# Ad_Hoc_Radio_Node_2005.net
KiCad netlist of a schematic drawn in Altium Designer
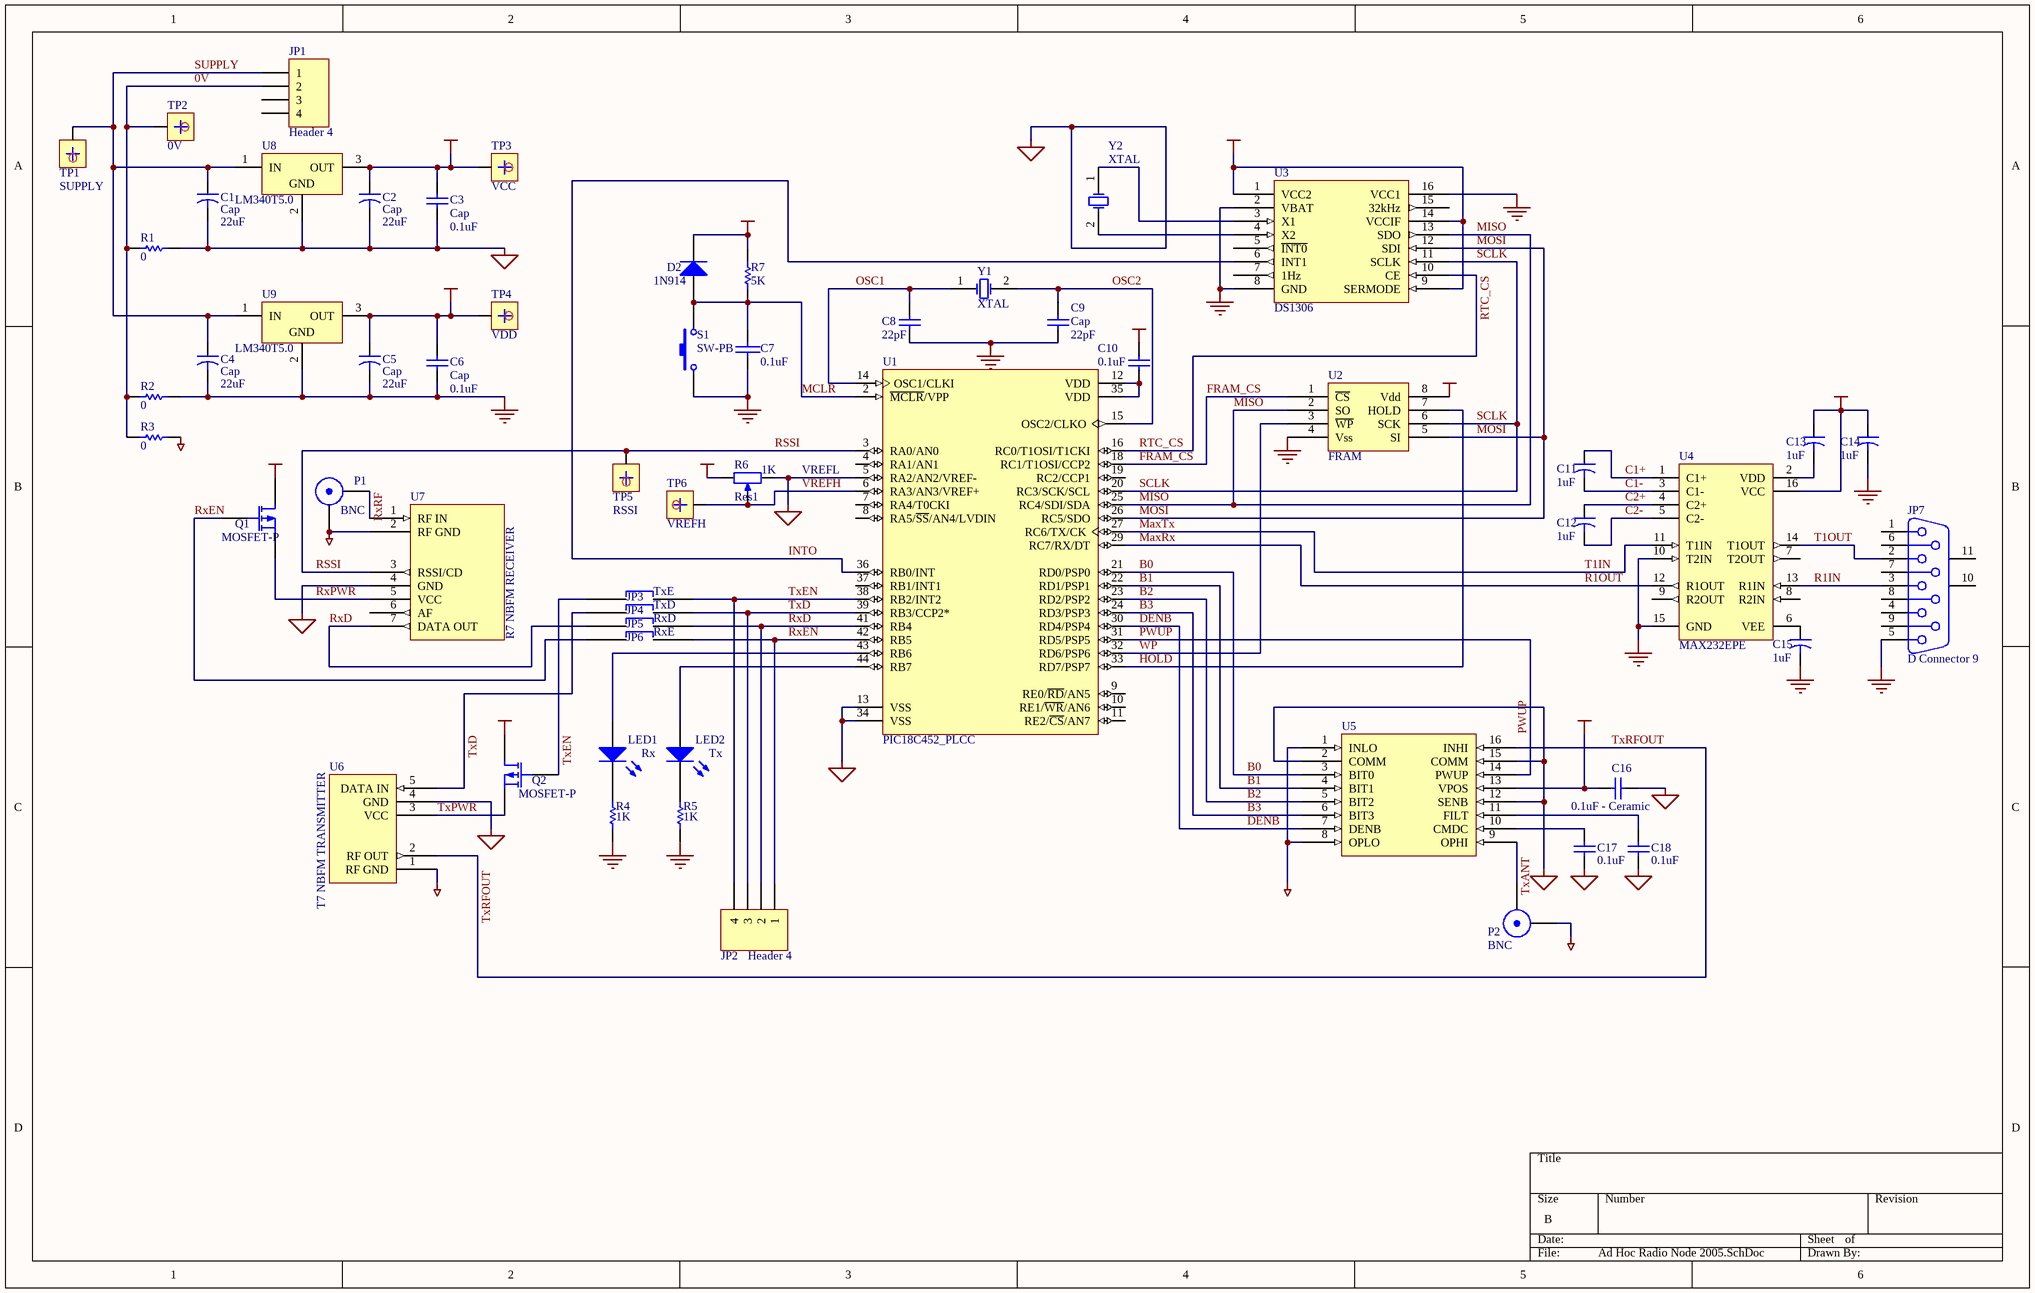
[diagram p0: Ad Hoc Radio Node 2005.SchDoc]

(export (version "E")
  (design (tool "Eeschema 10.0.6"))
  (components
    (comp (ref "C1")
      (value "Cap")
      (footprint "0.1 ELECTRO CAP")
      (description "Capacitor")
      (fields
        (field (name "MANUFACTURER") "Generic Components")
        (field (name "ALTIUM_VALUE") "22uF")
        (field (name "PUBLISHER") "Altium Limited")
      )
      (libsource (lib "Miscellaneous Devices") (part "Cap2"))
    )
    (comp (ref "C2")
      (value "Cap")
      (footprint "0.1 ELECTRO CAP")
      (description "Capacitor")
      (fields
        (field (name "MANUFACTURER") "Generic Components")
        (field (name "ALTIUM_VALUE") "22uF")
        (field (name "PUBLISHER") "Altium Limited")
      )
      (libsource (lib "Miscellaneous Devices") (part "Cap2"))
    )
    (comp (ref "C3")
      (value "Cap")
      (footprint "0.2 box cap")
      (description "Capacitor")
      (fields
        (field (name "MANUFACTURER") "Generic Components")
        (field (name "ALTIUM_VALUE") "0.1uF")
        (field (name "PUBLISHER") "Altium Limited")
      )
      (libsource (lib "Miscellaneous Devices") (part "Cap"))
    )
    (comp (ref "C4")
      (value "Cap")
      (footprint "0.1 RAD CAP")
      (description "Capacitor")
      (fields
        (field (name "MANUFACTURER") "Generic Components")
        (field (name "ALTIUM_VALUE") "22uF")
        (field (name "PUBLISHER") "Altium Limited")
      )
      (libsource (lib "Miscellaneous Devices") (part "Cap2"))
    )
    (comp (ref "C5")
      (value "Cap")
      (footprint "0.1 RAD CAP")
      (description "Capacitor")
      (fields
        (field (name "MANUFACTURER") "Generic Components")
        (field (name "ALTIUM_VALUE") "22uF")
        (field (name "PUBLISHER") "Altium Limited")
      )
      (libsource (lib "Miscellaneous Devices") (part "Cap2"))
    )
    (comp (ref "C6")
      (value "Cap")
      (footprint "0.2 box cap")
      (description "Capacitor")
      (fields
        (field (name "MANUFACTURER") "Generic Components")
        (field (name "ALTIUM_VALUE") "0.1uF")
        (field (name "PUBLISHER") "Altium Limited")
      )
      (libsource (lib "Miscellaneous Devices") (part "Cap"))
    )
    (comp (ref "C7")
      (value "0.1uF")
      (footprint "0.2 box cap")
      (description "Capacitor")
      (libsource (lib "*") (part "CAP"))
    )
    (comp (ref "C8")
      (value "Cap")
      (footprint "0.2 box cap")
      (description "Capacitor")
      (fields
        (field (name "MANUFACTURER") "Generic Components")
        (field (name "ALTIUM_VALUE") "22pF")
        (field (name "PUBLISHER") "Altium Limited")
      )
      (libsource (lib "Miscellaneous Devices") (part "Cap"))
    )
    (comp (ref "C9")
      (value "Cap")
      (footprint "0.2 box cap")
      (description "Capacitor")
      (fields
        (field (name "MANUFACTURER") "Generic Components")
        (field (name "ALTIUM_VALUE") "22pF")
        (field (name "PUBLISHER") "Altium Limited")
      )
      (libsource (lib "Miscellaneous Devices") (part "Cap"))
    )
    (comp (ref "C10")
      (value "0.1uF")
      (footprint "0.3 BOX CAP")
      (description "Capacitor")
      (fields (field (name "MANUFACTURER") "Generic Components") (field (name "PUBLISHER") "Altium Limited"))
      (libsource (lib "Miscellaneous Devices") (part "Cap"))
    )
    (comp (ref "C11")
      (value "Cap2")
      (footprint "0.1 RAD CAP")
      (description "Capacitor")
      (fields
        (field (name "MANUFACTURER") "Generic Components")
        (field (name "ALTIUM_VALUE") "1uF")
        (field (name "PUBLISHER") "Altium Limited")
      )
      (libsource (lib "Miscellaneous Devices") (part "Cap2"))
    )
    (comp (ref "C12")
      (value "Cap2")
      (footprint "0.1 RAD CAP")
      (description "Capacitor")
      (fields
        (field (name "MANUFACTURER") "Generic Components")
        (field (name "ALTIUM_VALUE") "1uF")
        (field (name "PUBLISHER") "Altium Limited")
      )
      (libsource (lib "Miscellaneous Devices") (part "Cap2"))
    )
    (comp (ref "C13")
      (value "Cap2")
      (footprint "0.1 RAD CAP")
      (description "Capacitor")
      (fields
        (field (name "MANUFACTURER") "Generic Components")
        (field (name "ALTIUM_VALUE") "1uF")
        (field (name "PUBLISHER") "Altium Limited")
      )
      (libsource (lib "Miscellaneous Devices") (part "Cap2"))
    )
    (comp (ref "C14")
      (value "Cap2")
      (footprint "0.1 RAD CAP")
      (description "Capacitor")
      (fields
        (field (name "MANUFACTURER") "Generic Components")
        (field (name "ALTIUM_VALUE") "1uF")
        (field (name "PUBLISHER") "Altium Limited")
      )
      (libsource (lib "Miscellaneous Devices") (part "Cap2"))
    )
    (comp (ref "C15")
      (value "Cap2")
      (footprint "0.1 RAD CAP")
      (description "Capacitor")
      (fields
        (field (name "MANUFACTURER") "Generic Components")
        (field (name "ALTIUM_VALUE") "1uF")
        (field (name "PUBLISHER") "Altium Limited")
      )
      (libsource (lib "Miscellaneous Devices") (part "Cap2"))
    )
    (comp (ref "C16")
      (value "0.1uF - Ceramic")
      (footprint "0.2 box cap")
      (description "Capacitor")
      (fields (field (name "MANUFACTURER") "Generic Components") (field (name "PUBLISHER") "Altium Limited"))
      (libsource (lib "Miscellaneous Devices") (part "Cap"))
    )
    (comp (ref "C17")
      (value "0.1uF")
      (footprint "0.2 box cap")
      (description "Capacitor")
      (fields (field (name "MANUFACTURER") "Generic Components") (field (name "PUBLISHER") "Altium Limited"))
      (libsource (lib "Miscellaneous Devices") (part "Cap"))
    )
    (comp (ref "C18")
      (value "0.1uF")
      (footprint "0.2 box cap")
      (description "Capacitor")
      (fields (field (name "MANUFACTURER") "Generic Components") (field (name "PUBLISHER") "Altium Limited"))
      (libsource (lib "Miscellaneous Devices") (part "Cap"))
    )
    (comp (ref "D2")
      (value "1N914")
      (footprint "AXIAL-0.4")
      (description "Default Diode")
      (fields (field (name "MANUFACTURER") "Generic Components") (field (name "PUBLISHER") "Altium Limited"))
      (libsource (lib "Miscellaneous Devices") (part "Diode"))
    )
    (comp (ref "JP1")
      (value "Header 4")
      (footprint "4 Way Terminal Block")
      (description "Header, 4-Pin")
      (fields (field (name "MANUFACTURER") "Generic Components") (field (name "PUBLISHER") "Altium Limited"))
      (libsource (lib "") (part "Header 4_1"))
    )
    (comp (ref "JP2")
      (value "Header 4")
      (footprint "4 Way Terminal Block")
      (description "Header, 4-Pin")
      (fields (field (name "MANUFACTURER") "Generic Components") (field (name "PUBLISHER") "Altium Limited"))
      (libsource (lib "Miscellaneous Connectors") (part "Header 4"))
    )
    (comp (ref "JP3")
      (value "TxE")
      (footprint "PCBComponent_1")
      (libsource (lib "2005Parts") (part "JUMPER"))
    )
    (comp (ref "JP4")
      (value "TxD")
      (footprint "PCBComponent_1")
      (libsource (lib "2005Parts") (part "JUMPER"))
    )
    (comp (ref "JP5")
      (value "RxD")
      (footprint "PCBComponent_1")
      (libsource (lib "2005Parts") (part "JUMPER"))
    )
    (comp (ref "JP6")
      (value "RxE")
      (footprint "PCBComponent_1")
      (libsource (lib "2005Parts") (part "JUMPER"))
    )
    (comp (ref "JP7")
      (value "D Connector 9")
      (footprint "DSUB1.385-2H9")
      (description "Receptacle Assembly, 9 Position, Right Angle")
      (fields (field (name "MANUFACTURER") "Generic Components") (field (name "PUBLISHER") "Altium Limited"))
      (libsource (lib "Miscellaneous Connectors") (part "D Connector 9"))
    )
    (comp (ref "LED1")
      (value "Rx")
      (footprint "Std LED")
      (description "Typical RED, GREEN, YELLOW, AMBER GaAs LED")
      (fields (field (name "MANUFACTURER") "Generic Components") (field (name "PUBLISHER") "Altium Limited"))
      (libsource (lib "Miscellaneous Devices") (part "LED2"))
    )
    (comp (ref "LED2")
      (value "Tx")
      (footprint "Std LED")
      (description "Typical RED, GREEN, YELLOW, AMBER GaAs LED")
      (fields (field (name "MANUFACTURER") "Generic Components") (field (name "PUBLISHER") "Altium Limited"))
      (libsource (lib "Miscellaneous Devices") (part "LED2"))
    )
    (comp (ref "P1")
      (value "BNC")
      (footprint "PCB BNC Connector - duplicate")
      (description "BNC Elbow Connector")
      (fields (field (name "MANUFACTURER") "Generic Components") (field (name "PUBLISHER") "Altium Limited"))
      (libsource (lib "Miscellaneous Connectors") (part "BNC"))
    )
    (comp (ref "P2")
      (value "BNC")
      (footprint "PCB BNC Connector - duplicate")
      (description "BNC Elbow Connector")
      (fields (field (name "MANUFACTURER") "Generic Components") (field (name "PUBLISHER") "Altium Limited"))
      (libsource (lib "Miscellaneous Connectors") (part "BNC"))
    )
    (comp (ref "Q1")
      (value "MOSFET-P")
      (footprint "MOSFET")
      (description "P-Channel MOSFET")
      (fields (field (name "MANUFACTURER") "Generic Components") (field (name "PUBLISHER") "Altium Limited"))
      (libsource (lib "Miscellaneous Devices") (part "MOSFET-P"))
    )
    (comp (ref "Q2")
      (value "MOSFET-P")
      (footprint "MOSFET")
      (description "P-Channel MOSFET")
      (fields (field (name "MANUFACTURER") "Generic Components") (field (name "PUBLISHER") "Altium Limited"))
      (libsource (lib "Miscellaneous Devices") (part "MOSFET-P"))
    )
    (comp (ref "R1")
      (value "0")
      (footprint "AXIAL-0.3")
      (description "Resistor")
      (fields (field (name "MANUFACTURER") "Generic Components") (field (name "PUBLISHER") "Altium Limited"))
      (libsource (lib "Miscellaneous Devices") (part "Res1"))
    )
    (comp (ref "R2")
      (value "0")
      (footprint "AXIAL-0.3")
      (description "Resistor")
      (fields (field (name "MANUFACTURER") "Generic Components") (field (name "PUBLISHER") "Altium Limited"))
      (libsource (lib "Miscellaneous Devices") (part "Res1"))
    )
    (comp (ref "R3")
      (value "0")
      (footprint "AXIAL-0.3")
      (description "Resistor")
      (fields (field (name "MANUFACTURER") "Generic Components") (field (name "PUBLISHER") "Altium Limited"))
      (libsource (lib "Miscellaneous Devices") (part "Res1"))
    )
    (comp (ref "R4")
      (value "1K")
      (footprint "AXIAL-0.3")
      (description "Resistor")
      (fields (field (name "MANUFACTURER") "Generic Components") (field (name "PUBLISHER") "Altium Limited"))
      (libsource (lib "Miscellaneous Devices") (part "Res1"))
    )
    (comp (ref "R5")
      (value "1K")
      (footprint "AXIAL-0.3")
      (description "Resistor")
      (fields (field (name "MANUFACTURER") "Generic Components") (field (name "PUBLISHER") "Altium Limited"))
      (libsource (lib "Miscellaneous Devices") (part "Res1"))
    )
    (comp (ref "R6")
      (value "Res1")
      (footprint "VR2")
      (description "Potentiometer")
      (fields
        (field (name "MANUFACTURER") "Generic Components")
        (field (name "ALTIUM_VALUE") "1K")
        (field (name "PUBLISHER") "Altium Limited")
      )
      (libsource (lib "Miscellaneous Devices") (part "RPot2"))
    )
    (comp (ref "R7")
      (value "Res1")
      (footprint "AXIAL-0.3")
      (description "Resistor")
      (fields
        (field (name "MANUFACTURER") "Generic Components")
        (field (name "ALTIUM_VALUE") "5K")
        (field (name "PUBLISHER") "Altium Limited")
      )
      (libsource (lib "Miscellaneous Devices") (part "Res1"))
    )
    (comp (ref "S1")
      (value "SW-PB")
      (footprint "Reset Switch - duplicate")
      (description "Switch")
      (fields (field (name "MANUFACTURER") "Generic Components") (field (name "PUBLISHER") "Altium Limited"))
      (libsource (lib "Miscellaneous Devices") (part "SW-PB"))
    )
    (comp (ref "TP1")
      (value "SUPPLY")
      (footprint "TESTPOINT")
      (description "Test Point")
      (libsource (lib "") (part "TESTPOINT_2"))
    )
    (comp (ref "TP2")
      (value "0V")
      (footprint "TESTPOINT")
      (description "Test Point")
      (libsource (lib "PeteSchLib") (part "TESTPOINT"))
    )
    (comp (ref "TP3")
      (value "VCC")
      (footprint "TESTPOINT")
      (description "Test Point")
      (libsource (lib "PeteSchLib") (part "TESTPOINT"))
    )
    (comp (ref "TP4")
      (value "VDD")
      (footprint "TESTPOINT")
      (description "Test Point")
      (libsource (lib "PeteSchLib") (part "TESTPOINT"))
    )
    (comp (ref "TP5")
      (value "RSSI")
      (footprint "TESTPOINT")
      (description "Test Point")
      (libsource (lib "") (part "TESTPOINT_2"))
    )
    (comp (ref "TP6")
      (value "VREFH")
      (footprint "TESTPOINT")
      (description "Test Point")
      (libsource (lib "") (part "TESTPOINT_1"))
    )
    (comp (ref "U1")
      (value "PIC18C452_PLCC")
      (footprint "PIC18C452_PLCC - duplicate")
      (libsource (lib "Ad_Hoc_Parts") (part "PIC18C452_PLCC"))
    )
    (comp (ref "U2") (value "FRAM") (footprint "Ramtron FRAM") (libsource (lib "Ad_Hoc_Parts") (part "FRAM")))
    (comp (ref "U3") (value "DS1306") (footprint "DIP-16") (libsource (lib "2005Parts") (part "DS1306")))
    (comp (ref "U4")
      (value "MAX232EPE")
      (footprint "DIP-16")
      (description "+5V Powered RS-232 Driver/Receiver")
      (fields (field (name "MANUFACTURER") "Maxim") (field (name "PUBLISHER") "Altium Limited"))
      (libsource (lib "Maxim Communication Transceiver") (part "MAX232EPE"))
    )
    (comp (ref "U5")
      (value "~")
      (footprint "DIP16-Adaptor")
      (libsource (lib "Ad_Hoc_Parts") (part "AD8369_DIGITAL_CONT_PWR_AMP"))
    )
    (comp (ref "U6")
      (value "T7 NBFM TRANSMITTER")
      (footprint "T7")
      (libsource (lib "2005Parts") (part "T7 NBFM TRANSMITTER"))
    )
    (comp (ref "U7")
      (value "R7 NBFM RECEIVER")
      (footprint "R7 NBFM RECEIVER")
      (libsource (lib "2005Parts") (part "R7 NBFM RECEIVER"))
    )
    (comp (ref "U8")
      (value "LM340T5.0")
      (footprint "SFM-T3/A4.7V")
      (description "Series 3-Terminal Positive Regulator")
      (fields
        (field (name "MANUFACTURER") "National Semiconductor")
        (field (name "PUBLISHER") "Altium Limited")
      )
      (libsource (lib "NSC Power Mgt Voltage Regulator") (part "LM340T5.0"))
    )
    (comp (ref "U9")
      (value "LM340T5.0")
      (footprint "SFM-T3/A4.7V")
      (description "Series 3-Terminal Positive Regulator")
      (fields
        (field (name "MANUFACTURER") "National Semiconductor")
        (field (name "PUBLISHER") "Altium Limited")
      )
      (libsource (lib "NSC Power Mgt Voltage Regulator") (part "LM340T5.0"))
    )
    (comp (ref "Y1")
      (value "XTAL")
      (footprint "XTAL")
      (description "Crystal Oscillator")
      (fields (field (name "MANUFACTURER") "Generic Components") (field (name "PUBLISHER") "Altium Limited"))
      (libsource (lib "Miscellaneous Devices") (part "XTAL"))
    )
    (comp (ref "Y2")
      (value "XTAL")
      (footprint "2005Parts:XTAL")
      (description "Crystal Oscillator")
      (fields (field (name "MANUFACTURER") "Generic Components") (field (name "PUBLISHER") "Altium Limited"))
      (libsource (lib "Miscellaneous Devices") (part "XTAL"))
    )
  )
  (nets
    (net (code "1") (name "/0V") (class "Default")
      (node (ref "JP1") (pin "2") (pinfunction "2_2") (pintype "passive"))
      (node (ref "R1") (pin "1") (pinfunction "1_1") (pintype "passive"))
      (node (ref "R2") (pin "1") (pinfunction "1_1") (pintype "passive"))
      (node (ref "R3") (pin "1") (pinfunction "1_1") (pintype "passive"))
      (node (ref "TP2") (pin "1") (pinfunction "TP_1") (pintype "passive"))
    )
    (net (code "2") (name "/B0") (class "Default")
      (node (ref "U1") (pin "21") (pinfunction "RD0/PSP0_21") (pintype "bidirectional"))
      (node (ref "U5") (pin "3") (pinfunction "BIT0_3") (pintype "input"))
    )
    (net (code "3") (name "/B1") (class "Default")
      (node (ref "U1") (pin "22") (pinfunction "RD1/PSP1_22") (pintype "bidirectional"))
      (node (ref "U5") (pin "4") (pinfunction "BIT1_4") (pintype "input"))
    )
    (net (code "4") (name "/B2") (class "Default")
      (node (ref "U1") (pin "23") (pinfunction "RD2/PSP2_23") (pintype "bidirectional"))
      (node (ref "U5") (pin "5") (pinfunction "BIT2_5") (pintype "input"))
    )
    (net (code "5") (name "/B3") (class "Default")
      (node (ref "U1") (pin "24") (pinfunction "RD3/PSP3_24") (pintype "bidirectional"))
      (node (ref "U5") (pin "6") (pinfunction "BIT3_6") (pintype "input"))
    )
    (net (code "6") (name "/C1+") (class "Default")
      (node (ref "C11") (pin "1") (pinfunction "1_1") (pintype "passive"))
      (node (ref "U4") (pin "1") (pinfunction "C1+_1") (pintype "passive"))
    )
    (net (code "7") (name "/C1-") (class "Default")
      (node (ref "C11") (pin "2") (pinfunction "2_2") (pintype "passive"))
      (node (ref "U4") (pin "3") (pinfunction "C1-_3") (pintype "passive"))
    )
    (net (code "8") (name "/C2+") (class "Default")
      (node (ref "C12") (pin "1") (pinfunction "1_1") (pintype "passive"))
      (node (ref "U4") (pin "4") (pinfunction "C2+_4") (pintype "passive"))
    )
    (net (code "9") (name "/C2-") (class "Default")
      (node (ref "C12") (pin "2") (pinfunction "2_2") (pintype "passive"))
      (node (ref "U4") (pin "5") (pinfunction "C2-_5") (pintype "passive"))
    )
    (net (code "10") (name "/DENB") (class "Default")
      (node (ref "U1") (pin "30") (pinfunction "RD4/PSP4_30") (pintype "bidirectional"))
      (node (ref "U5") (pin "7") (pinfunction "DENB_7") (pintype "input"))
    )
    (net (code "11") (name "/FRAM_CS") (class "Default")
      (node (ref "U1") (pin "18") (pinfunction "RC1/T1OSI/CCP2_18") (pintype "bidirectional"))
      (node (ref "U2") (pin "1") (pinfunction "~{CS}_1") (pintype "passive"))
    )
    (net (code "12") (name "/HOLD") (class "Default")
      (node (ref "U1") (pin "33") (pinfunction "RD7/PSP7_33") (pintype "bidirectional"))
      (node (ref "U2") (pin "7") (pinfunction "HOLD_7") (pintype "passive"))
    )
    (net (code "13") (name "/INTO") (class "Default")
      (node (ref "U1") (pin "36") (pinfunction "RB0/INT_36") (pintype "bidirectional"))
      (node (ref "U3") (pin "6") (pinfunction "INT1_6") (pintype "output"))
    )
    (net (code "14") (name "/MCLR") (class "Default")
      (node (ref "C7") (pin "1") (pinfunction "1_1") (pintype "passive"))
      (node (ref "D2") (pin "1") (pinfunction "A_1") (pintype "passive"))
      (node (ref "R7") (pin "1") (pinfunction "1_1") (pintype "passive"))
      (node (ref "S1") (pin "2") (pinfunction "2_2") (pintype "passive"))
      (node (ref "U1") (pin "2") (pinfunction "~{MCLR}/VPP_2") (pintype "input"))
    )
    (net (code "15") (name "/MISO") (class "Default")
      (node (ref "U1") (pin "25") (pinfunction "RC4/SDI/SDA_25") (pintype "bidirectional"))
      (node (ref "U2") (pin "2") (pinfunction "SO_2") (pintype "passive"))
      (node (ref "U3") (pin "13") (pinfunction "SDO_13") (pintype "output"))
    )
    (net (code "16") (name "/MOSI") (class "Default")
      (node (ref "U1") (pin "26") (pinfunction "RC5/SDO_26") (pintype "bidirectional"))
      (node (ref "U2") (pin "5") (pinfunction "SI_5") (pintype "passive"))
      (node (ref "U3") (pin "12") (pinfunction "SDI_12") (pintype "input"))
    )
    (net (code "17") (name "/MaxRx") (class "Default")
      (node (ref "U1") (pin "29") (pinfunction "RC7/RX/DT_29") (pintype "bidirectional"))
      (node (ref "U4") (pin "12") (pinfunction "R1OUT_12") (pintype "output"))
    )
    (net (code "18") (name "/MaxTx") (class "Default")
      (node (ref "U1") (pin "27") (pinfunction "RC6/TX/CK_27") (pintype "bidirectional"))
      (node (ref "U4") (pin "11") (pinfunction "T1IN_11") (pintype "input"))
    )
    (net (code "19") (name "/OSC1") (class "Default")
      (node (ref "C8") (pin "2") (pinfunction "2_2") (pintype "passive"))
      (node (ref "U1") (pin "14") (pinfunction "OSC1/CLKI_14") (pintype "input"))
      (node (ref "Y1") (pin "1") (pinfunction "OSC1_1") (pintype "passive"))
    )
    (net (code "20") (name "/OSC2") (class "Default")
      (node (ref "C9") (pin "2") (pinfunction "2_2") (pintype "passive"))
      (node (ref "U1") (pin "15") (pinfunction "OSC2/CLKO_15") (pintype "output"))
      (node (ref "Y1") (pin "2") (pinfunction "OSC2_2") (pintype "passive"))
    )
    (net (code "21") (name "/PWUP") (class "Default")
      (node (ref "U1") (pin "31") (pinfunction "RD5/PSP5_31") (pintype "bidirectional"))
      (node (ref "U5") (pin "14") (pinfunction "PWUP_14") (pintype "input"))
    )
    (net (code "22") (name "/R1IN") (class "Default")
      (node (ref "JP7") (pin "3") (pinfunction "3_3") (pintype "passive"))
      (node (ref "U4") (pin "13") (pinfunction "R1IN_13") (pintype "input"))
    )
    (net (code "23") (name "/RSSI") (class "Default")
      (node (ref "TP5") (pin "1") (pinfunction "TP_1") (pintype "passive"))
      (node (ref "U1") (pin "3") (pinfunction "RA0/AN0_3") (pintype "bidirectional"))
      (node (ref "U7") (pin "3") (pinfunction "RSSI/CD_3") (pintype "output"))
    )
    (net (code "24") (name "/RTC_CS") (class "Default")
      (node (ref "U1") (pin "16") (pinfunction "RC0/T1OSI/T1CKI_16") (pintype "bidirectional"))
      (node (ref "U3") (pin "10") (pinfunction "CE_10") (pintype "input"))
    )
    (net (code "25") (name "/RxD") (class "Default")
      (node (ref "JP2") (pin "2") (pinfunction "2_2") (pintype "passive"))
      (node (ref "JP5") (pin "1") (pinfunction "1_1") (pintype "passive"))
      (node (ref "JP5") (pin "2") (pinfunction "2_2") (pintype "passive"))
      (node (ref "U1") (pin "41") (pinfunction "RB4_41") (pintype "bidirectional"))
      (node (ref "U7") (pin "7") (pinfunction "DATA_OUT_7") (pintype "output"))
    )
    (net (code "26") (name "/RxEN") (class "Default")
      (node (ref "JP2") (pin "1") (pinfunction "1_1") (pintype "passive"))
      (node (ref "JP6") (pin "1") (pinfunction "1_1") (pintype "passive"))
      (node (ref "JP6") (pin "2") (pinfunction "2_2") (pintype "passive"))
      (node (ref "Q1") (pin "2") (pinfunction "G_2") (pintype "passive"))
      (node (ref "U1") (pin "42") (pinfunction "RB5_42") (pintype "bidirectional"))
    )
    (net (code "27") (name "/RxPWR") (class "Default")
      (node (ref "Q1") (pin "3") (pinfunction "S_3") (pintype "passive"))
      (node (ref "U7") (pin "5") (pinfunction "VCC_5") (pintype "power_in"))
    )
    (net (code "28") (name "/RxRF") (class "Default")
      (node (ref "P1") (pin "1") (pinfunction "X_1") (pintype "passive"))
      (node (ref "U7") (pin "1") (pinfunction "RF_IN_1") (pintype "input"))
    )
    (net (code "29") (name "/SCLK") (class "Default")
      (node (ref "U1") (pin "20") (pinfunction "RC3/SCK/SCL_20") (pintype "bidirectional"))
      (node (ref "U2") (pin "6") (pinfunction "SCK_6") (pintype "passive"))
      (node (ref "U3") (pin "11") (pinfunction "SCLK_11") (pintype "input"))
    )
    (net (code "30") (name "/SUPPLY") (class "Default")
      (node (ref "C1") (pin "1") (pinfunction "1_1") (pintype "passive"))
      (node (ref "C4") (pin "1") (pinfunction "1_1") (pintype "passive"))
      (node (ref "JP1") (pin "1") (pinfunction "1_1") (pintype "passive"))
      (node (ref "TP1") (pin "1") (pinfunction "TP_1") (pintype "passive"))
      (node (ref "U8") (pin "1") (pinfunction "IN_1") (pintype "power_in"))
      (node (ref "U9") (pin "1") (pinfunction "IN_1") (pintype "power_in"))
    )
    (net (code "31") (name "/T1OUT") (class "Default")
      (node (ref "JP7") (pin "2") (pinfunction "2_2") (pintype "passive"))
      (node (ref "U4") (pin "14") (pinfunction "T1OUT_14") (pintype "output"))
    )
    (net (code "32") (name "/TxANT") (class "Default")
      (node (ref "P2") (pin "1") (pinfunction "X_1") (pintype "passive"))
      (node (ref "U5") (pin "9") (pinfunction "OPHI_9") (pintype "input"))
    )
    (net (code "33") (name "/TxD") (class "Default")
      (node (ref "JP2") (pin "3") (pinfunction "3_3") (pintype "passive"))
      (node (ref "JP4") (pin "1") (pinfunction "1_1") (pintype "passive"))
      (node (ref "JP4") (pin "2") (pinfunction "2_2") (pintype "passive"))
      (node (ref "U1") (pin "39") (pinfunction "RB3/CCP2*_39") (pintype "bidirectional"))
      (node (ref "U6") (pin "5") (pinfunction "DATA_IN_5") (pintype "input"))
    )
    (net (code "34") (name "/TxEN") (class "Default")
      (node (ref "JP2") (pin "4") (pinfunction "4_4") (pintype "passive"))
      (node (ref "JP3") (pin "1") (pinfunction "1_1") (pintype "passive"))
      (node (ref "JP3") (pin "2") (pinfunction "2_2") (pintype "passive"))
      (node (ref "Q2") (pin "2") (pinfunction "G_2") (pintype "passive"))
      (node (ref "U1") (pin "38") (pinfunction "RB2/INT2_38") (pintype "bidirectional"))
    )
    (net (code "35") (name "/TxPWR") (class "Default")
      (node (ref "Q2") (pin "3") (pinfunction "S_3") (pintype "passive"))
      (node (ref "U6") (pin "3") (pinfunction "VCC_3") (pintype "power_in"))
    )
    (net (code "36") (name "/TxRFOUT") (class "Default")
      (node (ref "U5") (pin "16") (pinfunction "INHI_16") (pintype "input"))
      (node (ref "U6") (pin "2") (pinfunction "RF_OUT_2") (pintype "output"))
    )
    (net (code "37") (name "/VREFH") (class "Default")
      (node (ref "R6") (pin "3") (pinfunction "TAP_3") (pintype "passive"))
      (node (ref "TP6") (pin "1") (pinfunction "TP_1") (pintype "passive"))
      (node (ref "U1") (pin "6") (pinfunction "RA3/AN3/VREF+_6") (pintype "bidirectional"))
    )
    (net (code "38") (name "/WP") (class "Default")
      (node (ref "U1") (pin "32") (pinfunction "RD6/PSP6_32") (pintype "bidirectional"))
      (node (ref "U2") (pin "3") (pinfunction "~{WP}_3") (pintype "passive"))
    )
    (net (code "39") (name "GND") (class "Default")
      (node (ref "C14") (pin "2") (pinfunction "2_2") (pintype "passive"))
      (node (ref "C15") (pin "2") (pinfunction "2_2") (pintype "passive"))
      (node (ref "C4") (pin "2") (pinfunction "2_2") (pintype "passive"))
      (node (ref "C5") (pin "2") (pinfunction "2_2") (pintype "passive"))
      (node (ref "C6") (pin "2") (pinfunction "2_2") (pintype "passive"))
      (node (ref "C7") (pin "2") (pinfunction "2_2") (pintype "passive"))
      (node (ref "C8") (pin "1") (pinfunction "1_1") (pintype "passive"))
      (node (ref "C9") (pin "1") (pinfunction "1_1") (pintype "passive"))
      (node (ref "JP7") (pin "5") (pinfunction "5_5") (pintype "passive"))
      (node (ref "R2") (pin "2") (pinfunction "2_2") (pintype "passive"))
      (node (ref "R4") (pin "2") (pinfunction "2_2") (pintype "passive"))
      (node (ref "R5") (pin "2") (pinfunction "2_2") (pintype "passive"))
      (node (ref "S1") (pin "1") (pinfunction "1_1") (pintype "passive"))
      (node (ref "U1") (pin "13") (pinfunction "VSS_13") (pintype "power_in"))
      (node (ref "U1") (pin "34") (pinfunction "VSS_34") (pintype "power_in"))
      (node (ref "U2") (pin "4") (pinfunction "Vss_4") (pintype "passive"))
      (node (ref "U3") (pin "16") (pinfunction "VCC1_16") (pintype "power_in"))
      (node (ref "U3") (pin "2") (pinfunction "VBAT_2") (pintype "power_in"))
      (node (ref "U3") (pin "8") (pinfunction "GND_8") (pintype "power_in"))
      (node (ref "U4") (pin "10") (pinfunction "T2IN_10") (pintype "input"))
      (node (ref "U4") (pin "15") (pinfunction "GND_15") (pintype "power_in"))
      (node (ref "U9") (pin "2") (pinfunction "GND_2") (pintype "power_in"))
    )
    (net (code "40") (name "Net-(C10-Pad2)") (class "Default")
      (node (ref "C10") (pin "2") (pinfunction "2_2") (pintype "passive"))
      (node (ref "U1") (pin "12") (pinfunction "VDD_12") (pintype "power_in"))
      (node (ref "U1") (pin "35") (pinfunction "VDD_35") (pintype "power_in"))
    )
    (net (code "41") (name "Net-(LED1-A)") (class "Default")
      (node (ref "LED1") (pin "1") (pinfunction "A_1") (pintype "passive"))
      (node (ref "U1") (pin "43") (pinfunction "RB6_43") (pintype "bidirectional"))
    )
    (net (code "42") (name "Net-(LED1-K)") (class "Default")
      (node (ref "LED1") (pin "2") (pinfunction "K_2") (pintype "passive"))
      (node (ref "R4") (pin "1") (pinfunction "1_1") (pintype "passive"))
    )
    (net (code "43") (name "Net-(LED2-A)") (class "Default")
      (node (ref "LED2") (pin "1") (pinfunction "A_1") (pintype "passive"))
      (node (ref "U1") (pin "44") (pinfunction "RB7_44") (pintype "bidirectional"))
    )
    (net (code "44") (name "Net-(LED2-K)") (class "Default")
      (node (ref "LED2") (pin "2") (pinfunction "K_2") (pintype "passive"))
      (node (ref "R5") (pin "1") (pinfunction "1_1") (pintype "passive"))
    )
    (net (code "45") (name "Net-(U3-X1)") (class "Default")
      (node (ref "U3") (pin "3") (pinfunction "X1_3") (pintype "input"))
      (node (ref "Y2") (pin "1") (pinfunction "OSC1_1") (pintype "passive"))
    )
    (net (code "46") (name "Net-(U3-X2)") (class "Default")
      (node (ref "U3") (pin "4") (pinfunction "X2_4") (pintype "input"))
      (node (ref "Y2") (pin "2") (pinfunction "OSC2_2") (pintype "passive"))
    )
    (net (code "47") (name "Net-(U4-VDD)") (class "Default")
      (node (ref "C13") (pin "2") (pinfunction "2_2") (pintype "passive"))
      (node (ref "U4") (pin "2") (pinfunction "VDD_2") (pintype "power_in"))
    )
    (net (code "48") (name "Net-(U4-VEE)") (class "Default")
      (node (ref "C15") (pin "1") (pinfunction "1_1") (pintype "passive"))
      (node (ref "U4") (pin "6") (pinfunction "VEE_6") (pintype "power_in"))
    )
    (net (code "49") (name "Net-(U5-CMDC)") (class "Default")
      (node (ref "C17") (pin "1") (pinfunction "1_1") (pintype "passive"))
      (node (ref "U5") (pin "10") (pinfunction "CMDC_10") (pintype "input"))
    )
    (net (code "50") (name "Net-(U5-FILT)") (class "Default")
      (node (ref "C18") (pin "1") (pinfunction "1_1") (pintype "passive"))
      (node (ref "U5") (pin "11") (pinfunction "FILT_11") (pintype "input"))
    )
    (net (code "51") (name "RFGND") (class "Default")
      (node (ref "P1") (pin "2") (pinfunction "Y_2") (pintype "passive"))
      (node (ref "P2") (pin "2") (pinfunction "Y_2") (pintype "passive"))
      (node (ref "R3") (pin "2") (pinfunction "2_2") (pintype "passive"))
      (node (ref "U5") (pin "1") (pinfunction "INLO_1") (pintype "input"))
      (node (ref "U5") (pin "8") (pinfunction "OPLO_8") (pintype "input"))
      (node (ref "U6") (pin "1") (pinfunction "RF_GND_1") (pintype "power_in"))
      (node (ref "U7") (pin "2") (pinfunction "RF_GND_2") (pintype "power_in"))
    )
    (net (code "52") (name "SGND") (class "Default")
      (node (ref "C1") (pin "2") (pinfunction "2_2") (pintype "passive"))
      (node (ref "C16") (pin "1") (pinfunction "1_1") (pintype "passive"))
      (node (ref "C17") (pin "2") (pinfunction "2_2") (pintype "passive"))
      (node (ref "C18") (pin "2") (pinfunction "2_2") (pintype "passive"))
      (node (ref "C2") (pin "2") (pinfunction "2_2") (pintype "passive"))
      (node (ref "C3") (pin "2") (pinfunction "2_2") (pintype "passive"))
      (node (ref "R1") (pin "2") (pinfunction "2_2") (pintype "passive"))
      (node (ref "R6") (pin "2") (pinfunction "BOT_2") (pintype "passive"))
      (node (ref "U1") (pin "5") (pinfunction "RA2/AN2/VREF-_5") (pintype "bidirectional"))
      (node (ref "U5") (pin "12") (pinfunction "SENB_12") (pintype "input"))
      (node (ref "U5") (pin "15") (pinfunction "COMM_15") (pintype "input"))
      (node (ref "U5") (pin "2") (pinfunction "COMM_2") (pintype "power_in"))
      (node (ref "U6") (pin "4") (pinfunction "GND_4") (pintype "power_in"))
      (node (ref "U7") (pin "4") (pinfunction "GND_4") (pintype "power_in"))
      (node (ref "U8") (pin "2") (pinfunction "GND_2") (pintype "power_in"))
    )
    (net (code "53") (name "VCC") (class "Default")
      (node (ref "C16") (pin "2") (pinfunction "2_2") (pintype "passive"))
      (node (ref "C2") (pin "1") (pinfunction "1_1") (pintype "passive"))
      (node (ref "C3") (pin "1") (pinfunction "1_1") (pintype "passive"))
      (node (ref "Q1") (pin "1") (pinfunction "D_1") (pintype "passive"))
      (node (ref "Q2") (pin "1") (pinfunction "D_1") (pintype "passive"))
      (node (ref "R6") (pin "1") (pinfunction "TOP_1") (pintype "passive"))
      (node (ref "TP3") (pin "1") (pinfunction "TP_1") (pintype "passive"))
      (node (ref "U5") (pin "13") (pinfunction "VPOS_13") (pintype "input"))
      (node (ref "U8") (pin "3") (pinfunction "OUT_3") (pintype "power_in"))
    )
    (net (code "54") (name "VDD") (class "Default")
      (node (ref "C10") (pin "1") (pinfunction "1_1") (pintype "passive"))
      (node (ref "C13") (pin "1") (pinfunction "1_1") (pintype "passive"))
      (node (ref "C14") (pin "1") (pinfunction "1_1") (pintype "passive"))
      (node (ref "C5") (pin "1") (pinfunction "1_1") (pintype "passive"))
      (node (ref "C6") (pin "1") (pinfunction "1_1") (pintype "passive"))
      (node (ref "D2") (pin "2") (pinfunction "K_2") (pintype "passive"))
      (node (ref "R7") (pin "2") (pinfunction "2_2") (pintype "passive"))
      (node (ref "TP4") (pin "1") (pinfunction "TP_1") (pintype "passive"))
      (node (ref "U2") (pin "8") (pinfunction "Vdd_8") (pintype "passive"))
      (node (ref "U3") (pin "1") (pinfunction "VCC2_1") (pintype "power_in"))
      (node (ref "U3") (pin "14") (pinfunction "VCCIF_14") (pintype "power_in"))
      (node (ref "U3") (pin "9") (pinfunction "SERMODE_9") (pintype "input"))
      (node (ref "U4") (pin "16") (pinfunction "VCC_16") (pintype "power_in"))
      (node (ref "U9") (pin "3") (pinfunction "OUT_3") (pintype "power_in"))
    )
    (net (code "55") (name "unconnected-(JP1-Pad3)") (class "Default")
      (node (ref "JP1") (pin "3") (pinfunction "3_3") (pintype "passive"))
    )
    (net (code "56") (name "unconnected-(JP1-Pad4)") (class "Default")
      (node (ref "JP1") (pin "4") (pinfunction "4_4") (pintype "passive"))
    )
    (net (code "57") (name "unconnected-(JP7-MH1-Pad10)") (class "Default")
      (node (ref "JP7") (pin "10") (pinfunction "MH1_10") (pintype "passive"))
    )
    (net (code "58") (name "unconnected-(JP7-MH2-Pad11)") (class "Default")
      (node (ref "JP7") (pin "11") (pinfunction "MH2_11") (pintype "passive"))
    )
    (net (code "59") (name "unconnected-(JP7-Pad1)") (class "Default")
      (node (ref "JP7") (pin "1") (pinfunction "1_1") (pintype "passive"))
    )
    (net (code "60") (name "unconnected-(JP7-Pad4)") (class "Default")
      (node (ref "JP7") (pin "4") (pinfunction "4_4") (pintype "passive"))
    )
    (net (code "61") (name "unconnected-(JP7-Pad6)") (class "Default")
      (node (ref "JP7") (pin "6") (pinfunction "6_6") (pintype "passive"))
    )
    (net (code "62") (name "unconnected-(JP7-Pad7)") (class "Default")
      (node (ref "JP7") (pin "7") (pinfunction "7_7") (pintype "passive"))
    )
    (net (code "63") (name "unconnected-(JP7-Pad8)") (class "Default")
      (node (ref "JP7") (pin "8") (pinfunction "8_8") (pintype "passive"))
    )
    (net (code "64") (name "unconnected-(JP7-Pad9)") (class "Default")
      (node (ref "JP7") (pin "9") (pinfunction "9_9") (pintype "passive"))
    )
    (net (code "65") (name "unconnected-(U1-RA1{slash}AN1-Pad4)") (class "Default")
      (node (ref "U1") (pin "4") (pinfunction "RA1/AN1_4") (pintype "bidirectional"))
    )
    (net (code "66") (name "unconnected-(U1-RA4{slash}T0CKI-Pad7)") (class "Default")
      (node (ref "U1") (pin "7") (pinfunction "RA4/T0CKI_7") (pintype "bidirectional"))
    )
    (net (code "67") (name "unconnected-(U1-RA5{slash}~{SS}{slash}AN4{slash}LVDIN-Pad8)") (class "Default")
      (node (ref "U1") (pin "8") (pinfunction "RA5/~{SS}/AN4/LVDIN_8") (pintype "bidirectional"))
    )
    (net (code "68") (name "unconnected-(U1-RB1{slash}INT1-Pad37)") (class "Default")
      (node (ref "U1") (pin "37") (pinfunction "RB1/INT1_37") (pintype "bidirectional"))
    )
    (net (code "69") (name "unconnected-(U1-RC2{slash}CCP1-Pad19)") (class "Default")
      (node (ref "U1") (pin "19") (pinfunction "RC2/CCP1_19") (pintype "bidirectional"))
    )
    (net (code "70") (name "unconnected-(U1-RE0{slash}~{RD}{slash}AN5-Pad9)") (class "Default")
      (node (ref "U1") (pin "9") (pinfunction "RE0/~{RD}/AN5_9") (pintype "bidirectional"))
    )
    (net (code "71") (name "unconnected-(U1-RE1{slash}~{WR}{slash}AN6-Pad10)") (class "Default")
      (node (ref "U1") (pin "10") (pinfunction "RE1/~{WR}/AN6_10") (pintype "bidirectional"))
    )
    (net (code "72") (name "unconnected-(U1-RE2{slash}~{CS}{slash}AN7-Pad11)") (class "Default")
      (node (ref "U1") (pin "11") (pinfunction "RE2/~{CS}/AN7_11") (pintype "bidirectional"))
    )
    (net (code "73") (name "unconnected-(U3-1Hz-Pad7)") (class "Default")
      (node (ref "U3") (pin "7") (pinfunction "1Hz_7") (pintype "output"))
    )
    (net (code "74") (name "unconnected-(U3-32kHz-Pad15)") (class "Default")
      (node (ref "U3") (pin "15") (pinfunction "32kHz_15") (pintype "output"))
    )
    (net (code "75") (name "unconnected-(U3-~{INT0}-Pad5)") (class "Default")
      (node (ref "U3") (pin "5") (pinfunction "~{INT0}_5") (pintype "output"))
    )
    (net (code "76") (name "unconnected-(U4-R2IN-Pad8)") (class "Default")
      (node (ref "U4") (pin "8") (pinfunction "R2IN_8") (pintype "input"))
    )
    (net (code "77") (name "unconnected-(U4-R2OUT-Pad9)") (class "Default")
      (node (ref "U4") (pin "9") (pinfunction "R2OUT_9") (pintype "output"))
    )
    (net (code "78") (name "unconnected-(U4-T2OUT-Pad7)") (class "Default")
      (node (ref "U4") (pin "7") (pinfunction "T2OUT_7") (pintype "output"))
    )
    (net (code "79") (name "unconnected-(U7-AF-Pad6)") (class "Default")
      (node (ref "U7") (pin "6") (pinfunction "AF_6") (pintype "output"))
    )
  )
)
